# legoPFremote.net
KiCad netlist of a schematic drawn in EAGLE
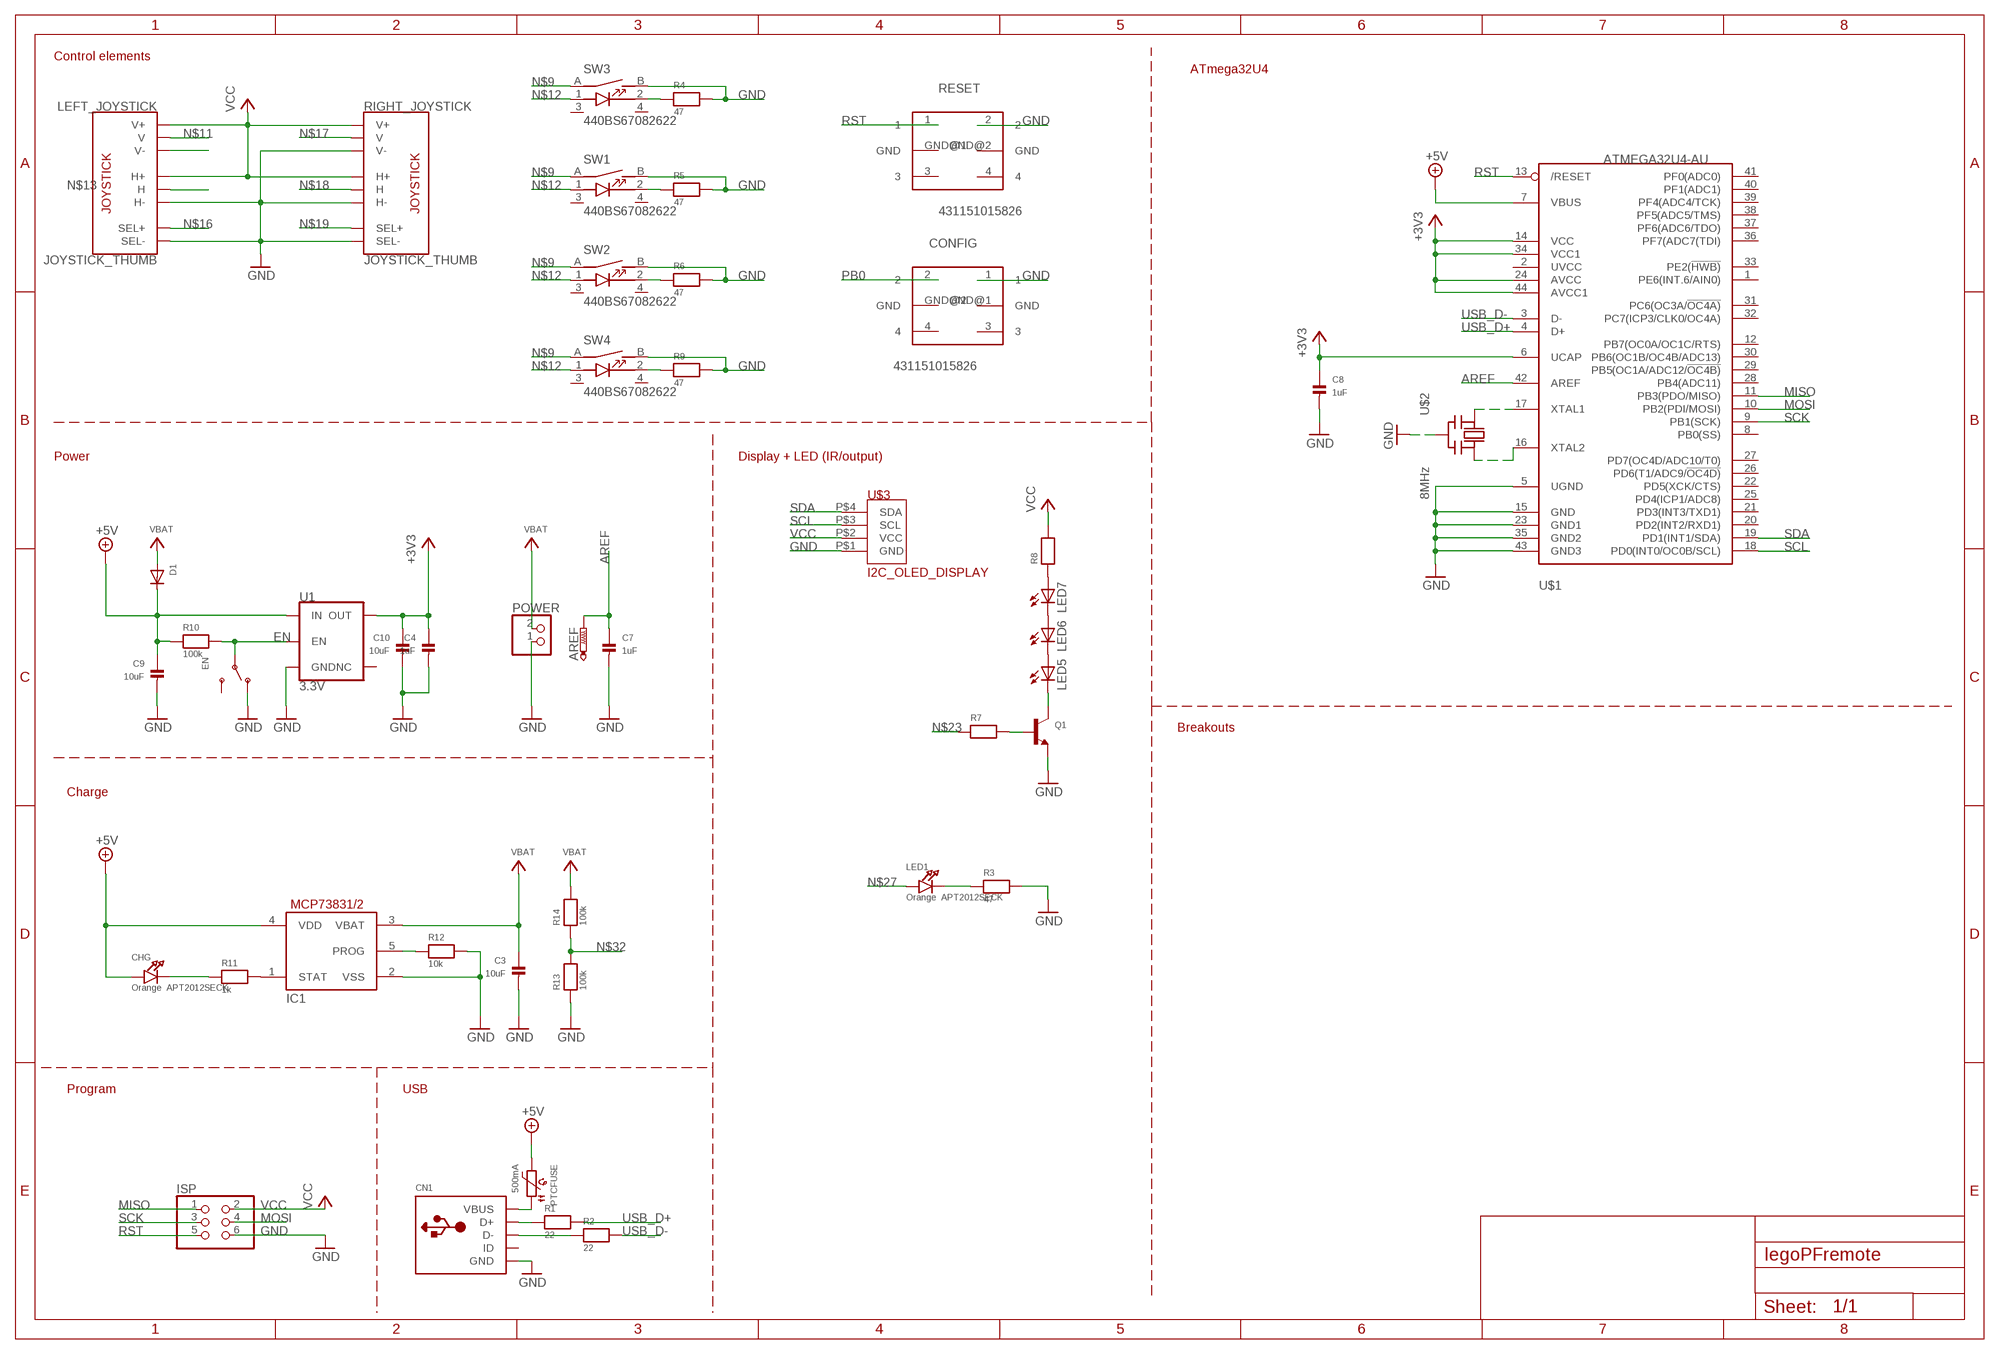
[diagram p0: schematic, sheet 1]

(export (version "E")
  (design (tool "Eeschema 10.0.6"))
  (components
    (comp (ref "AREF")
      (value "PTR1B1,27")
      (footprint "eagle-import:B1,27")
      (libsource (lib "eagle-import") (part "PTR1B1,27"))
    )
    (comp (ref "C3")
      (value "10uF")
      (footprint "eagle-import:0805")
      (libsource (lib "eagle-import") (part "CAP_CERAMIC0805"))
    )
    (comp (ref "C4")
      (value "1uF")
      (footprint "eagle-import:0805")
      (libsource (lib "eagle-import") (part "CAP_CERAMIC0805"))
    )
    (comp (ref "C7")
      (value "1uF")
      (footprint "eagle-import:0805")
      (libsource (lib "eagle-import") (part "CAP_CERAMIC0805"))
    )
    (comp (ref "C8")
      (value "1uF")
      (footprint "eagle-import:0805")
      (libsource (lib "eagle-import") (part "CAP_CERAMIC0805"))
    )
    (comp (ref "C9")
      (value "10uF")
      (footprint "eagle-import:0805")
      (libsource (lib "eagle-import") (part "CAP_CERAMIC0805"))
    )
    (comp (ref "C10")
      (value "10uF")
      (footprint "eagle-import:0805")
      (libsource (lib "eagle-import") (part "CAP_CERAMIC0805"))
    )
    (comp (ref "CHG")
      (value "Orange APT2012SECK")
      (footprint "eagle-import:CHIPLED_0805")
      (libsource (lib "eagle-import") (part "LED0805"))
    )
    (comp (ref "CN1")
      (value "USBMINIB")
      (footprint "eagle-import:USB-MINIB")
      (libsource (lib "eagle-import") (part "USBMINIB"))
    )
    (comp (ref "CONFIG")
      (value "431151015826")
      (footprint "eagle-import:431181015816")
      (libsource (lib "eagle-import") (part "431151015826"))
    )
    (comp (ref "D1")
      (value "DIODESOD-123")
      (footprint "eagle-import:SOD-123")
      (libsource (lib "eagle-import") (part "DIODESOD-123"))
    )
    (comp (ref "EN")
      (value "SWITCH_SPDT")
      (footprint "eagle-import:SPDT_SMT_SSSS811101")
      (libsource (lib "eagle-import") (part "SWITCH_SPDT"))
    )
    (comp (ref "IC1")
      (value "MCP73831/OT")
      (footprint "eagle-import:SOT23-5L")
      (libsource (lib "eagle-import") (part "MCP73831/OT"))
    )
    (comp (ref "ISP")
      (value "PINHD-2X3")
      (footprint "eagle-import:2X03")
      (libsource (lib "eagle-import") (part "PINHD-2X3"))
    )
    (comp (ref "LED1")
      (value "Orange APT2012SECK")
      (footprint "eagle-import:CHIPLED_0805")
      (libsource (lib "eagle-import") (part "LED0805"))
    )
    (comp (ref "LED5")
      (value "LEDIRL80A")
      (footprint "eagle-import:IRL80A")
      (libsource (lib "eagle-import") (part "LEDIRL80A"))
    )
    (comp (ref "LED6")
      (value "LEDIRL80A")
      (footprint "eagle-import:IRL80A")
      (libsource (lib "eagle-import") (part "LEDIRL80A"))
    )
    (comp (ref "LED7")
      (value "LEDIRL80A")
      (footprint "eagle-import:IRL80A")
      (libsource (lib "eagle-import") (part "LEDIRL80A"))
    )
    (comp (ref "LEFT_JOYSTICK")
      (value "JOYSTICK_THUMB")
      (footprint "eagle-import:JOYSTICK")
      (libsource (lib "eagle-import") (part "JOYSTICK_THUMB"))
    )
    (comp (ref "POWER")
      (value "JST_2PIN-THM")
      (footprint "eagle-import:JST-PH-2-THM")
      (libsource (lib "eagle-import") (part "JST_2PIN-THM"))
    )
    (comp (ref "PTCFUSE")
      (value "500mA")
      (footprint "eagle-import:1206")
      (libsource (lib "eagle-import") (part "PTC1206"))
    )
    (comp (ref "Q1")
      (value "TRANSISTOR_NPN")
      (footprint "eagle-import:SOT23-R")
      (libsource (lib "eagle-import") (part "TRANSISTOR_NPN"))
    )
    (comp (ref "R1")
      (value "22")
      (footprint "eagle-import:0805")
      (libsource (lib "eagle-import") (part "RESISTOR0805"))
    )
    (comp (ref "R2")
      (value "22")
      (footprint "eagle-import:0805")
      (libsource (lib "eagle-import") (part "RESISTOR0805"))
    )
    (comp (ref "R3")
      (value "47")
      (footprint "eagle-import:0805")
      (libsource (lib "eagle-import") (part "RESISTOR0805"))
    )
    (comp (ref "R4")
      (value "47")
      (footprint "eagle-import:0805")
      (libsource (lib "eagle-import") (part "RESISTOR0805"))
    )
    (comp (ref "R5")
      (value "47")
      (footprint "eagle-import:0805")
      (libsource (lib "eagle-import") (part "RESISTOR0805"))
    )
    (comp (ref "R6")
      (value "47")
      (footprint "eagle-import:0805")
      (libsource (lib "eagle-import") (part "RESISTOR0805"))
    )
    (comp (ref "R7")
      (value "RESISTOR0805")
      (footprint "eagle-import:0805")
      (libsource (lib "eagle-import") (part "RESISTOR0805"))
    )
    (comp (ref "R8")
      (value "RESISTOR0805")
      (footprint "eagle-import:0805")
      (libsource (lib "eagle-import") (part "RESISTOR0805"))
    )
    (comp (ref "R9")
      (value "47")
      (footprint "eagle-import:0805")
      (libsource (lib "eagle-import") (part "RESISTOR0805"))
    )
    (comp (ref "R10")
      (value "100k")
      (footprint "eagle-import:0805")
      (libsource (lib "eagle-import") (part "RESISTOR0805"))
    )
    (comp (ref "R11")
      (value "1k")
      (footprint "eagle-import:0805")
      (libsource (lib "eagle-import") (part "RESISTOR0805"))
    )
    (comp (ref "R12")
      (value "10k")
      (footprint "eagle-import:0805")
      (libsource (lib "eagle-import") (part "RESISTOR0805"))
    )
    (comp (ref "R13")
      (value "100k")
      (footprint "eagle-import:0805")
      (libsource (lib "eagle-import") (part "RESISTOR0805"))
    )
    (comp (ref "R14")
      (value "100k")
      (footprint "eagle-import:0805")
      (libsource (lib "eagle-import") (part "RESISTOR0805"))
    )
    (comp (ref "RESET")
      (value "431151015826")
      (footprint "eagle-import:431181015816")
      (libsource (lib "eagle-import") (part "431151015826"))
    )
    (comp (ref "RIGHT_JOYSTICK")
      (value "JOYSTICK_THUMB")
      (footprint "eagle-import:JOYSTICK")
      (libsource (lib "eagle-import") (part "JOYSTICK_THUMB"))
    )
    (comp (ref "SW1")
      (value "440BS67082622")
      (footprint "eagle-import:440BS67082622")
      (libsource (lib "eagle-import") (part "440BS67082622"))
    )
    (comp (ref "SW2")
      (value "440BS67082622")
      (footprint "eagle-import:440BS67082622")
      (libsource (lib "eagle-import") (part "440BS67082622"))
    )
    (comp (ref "SW3")
      (value "440BS67082622")
      (footprint "eagle-import:440BS67082622")
      (libsource (lib "eagle-import") (part "440BS67082622"))
    )
    (comp (ref "SW4")
      (value "440BS67082622")
      (footprint "eagle-import:440BS67082622")
      (libsource (lib "eagle-import") (part "440BS67082622"))
    )
    (comp (ref "U$1")
      (value "ATMEGA32U4-AU")
      (footprint "eagle-import:TQFP44")
      (libsource (lib "eagle-import") (part "ATMEGA32U4-AU"))
    )
    (comp (ref "U$2")
      (value "8MHz")
      (footprint "eagle-import:CSTCR-G")
      (libsource (lib "eagle-import") (part "CERMOSCILL-CSTCRG"))
    )
    (comp (ref "U$3")
      (value "I2C_OLED_DISPLAY")
      (footprint "eagle-import:HD1X4")
      (libsource (lib "eagle-import") (part "I2C_OLED_DISPLAY"))
    )
    (comp (ref "U1")
      (value "3.3V")
      (footprint "eagle-import:SOT23-5")
      (libsource (lib "eagle-import") (part "V_REG_AP2112K-3.3V"))
    )
  )
  (nets
    (net (code "1") (name "+3V3") (class "Default")
      (node (ref "C10") (pin "1") (pinfunction "P$1_1") (pintype "passive"))
      (node (ref "C4") (pin "1") (pinfunction "P$1_1") (pintype "passive"))
      (node (ref "C8") (pin "1") (pinfunction "P$1_1") (pintype "passive"))
      (node (ref "U$1") (pin "14") (pinfunction "VCC_14") (pintype "bidirectional"))
      (node (ref "U$1") (pin "24") (pinfunction "AVCC_24") (pintype "bidirectional"))
      (node (ref "U$1") (pin "34") (pinfunction "VCC1_34") (pintype "bidirectional"))
      (node (ref "U$1") (pin "44") (pinfunction "AVCC1_44") (pintype "bidirectional"))
      (node (ref "U$1") (pin "6") (pinfunction "UCAP_6") (pintype "bidirectional"))
      (node (ref "U1") (pin "5") (pinfunction "OUT_5") (pintype "passive"))
    )
    (net (code "2") (name "+5V") (class "Default")
      (node (ref "C9") (pin "1") (pinfunction "P$1_1") (pintype "passive"))
      (node (ref "CHG") (pin "A") (pinfunction "A_A") (pintype "passive"))
      (node (ref "D1") (pin "C") (pinfunction "C_C") (pintype "passive"))
      (node (ref "IC1") (pin "4") (pinfunction "VDD_4") (pintype "power_in"))
      (node (ref "PTCFUSE") (pin "2") (pinfunction "2_2") (pintype "passive"))
      (node (ref "R10") (pin "1") (pinfunction "1_1") (pintype "passive"))
      (node (ref "U$1") (pin "7") (pinfunction "VBUS_7") (pintype "bidirectional"))
      (node (ref "U1") (pin "1") (pinfunction "IN_1") (pintype "input"))
    )
    (net (code "3") (name "/AREF") (class "Default")
      (node (ref "AREF") (pin "TP") (pinfunction "TP_TP") (pintype "input"))
      (node (ref "C7") (pin "1") (pinfunction "P$1_1") (pintype "passive"))
      (node (ref "U$1") (pin "42") (pinfunction "AREF_42") (pintype "bidirectional"))
    )
    (net (code "4") (name "/EN") (class "Default")
      (node (ref "EN") (pin "B") (pinfunction "P_B") (pintype "passive"))
      (node (ref "R10") (pin "2") (pinfunction "2_2") (pintype "passive"))
      (node (ref "U1") (pin "3") (pinfunction "EN_3") (pintype "input"))
    )
    (net (code "5") (name "/MISO") (class "Default")
      (node (ref "ISP") (pin "1") (pinfunction "1_1") (pintype "passive"))
      (node (ref "U$1") (pin "11") (pinfunction "PB3(PDO/MISO)_11") (pintype "bidirectional"))
    )
    (net (code "6") (name "/MOSI") (class "Default")
      (node (ref "ISP") (pin "4") (pinfunction "4_4") (pintype "passive"))
      (node (ref "U$1") (pin "10") (pinfunction "PB2(PDI/MOSI)_10") (pintype "bidirectional"))
    )
    (net (code "7") (name "/N$9") (class "Default")
      (node (ref "SW1") (pin "A") (pinfunction "A_A") (pintype "passive"))
      (node (ref "SW2") (pin "A") (pinfunction "A_A") (pintype "passive"))
      (node (ref "SW3") (pin "A") (pinfunction "A_A") (pintype "passive"))
      (node (ref "SW4") (pin "A") (pinfunction "A_A") (pintype "passive"))
    )
    (net (code "8") (name "/N$11") (class "Default")
      (node (ref "LEFT_JOYSTICK") (pin "V2") (pinfunction "V_V2") (pintype "bidirectional"))
    )
    (net (code "9") (name "/N$12") (class "Default")
      (node (ref "SW1") (pin "1") (pinfunction "1_1") (pintype "passive"))
      (node (ref "SW2") (pin "1") (pinfunction "1_1") (pintype "passive"))
      (node (ref "SW3") (pin "1") (pinfunction "1_1") (pintype "passive"))
      (node (ref "SW4") (pin "1") (pinfunction "1_1") (pintype "passive"))
    )
    (net (code "10") (name "/N$13") (class "Default")
      (node (ref "LEFT_JOYSTICK") (pin "H2") (pinfunction "H_H2") (pintype "bidirectional"))
    )
    (net (code "11") (name "/N$16") (class "Default")
      (node (ref "LEFT_JOYSTICK") (pin "B1A") (pinfunction "SEL+_B1A") (pintype "bidirectional"))
    )
    (net (code "12") (name "/N$17") (class "Default")
      (node (ref "RIGHT_JOYSTICK") (pin "V2") (pinfunction "V_V2") (pintype "bidirectional"))
    )
    (net (code "13") (name "/N$18") (class "Default")
      (node (ref "RIGHT_JOYSTICK") (pin "H2") (pinfunction "H_H2") (pintype "bidirectional"))
    )
    (net (code "14") (name "/N$19") (class "Default")
      (node (ref "RIGHT_JOYSTICK") (pin "B1A") (pinfunction "SEL+_B1A") (pintype "bidirectional"))
    )
    (net (code "15") (name "/N$23") (class "Default")
      (node (ref "R7") (pin "1") (pinfunction "1_1") (pintype "passive"))
    )
    (net (code "16") (name "/N$27") (class "Default")
      (node (ref "LED1") (pin "A") (pinfunction "A_A") (pintype "passive"))
    )
    (net (code "17") (name "/N$32") (class "Default")
      (node (ref "R13") (pin "2") (pinfunction "2_2") (pintype "passive"))
      (node (ref "R14") (pin "1") (pinfunction "1_1") (pintype "passive"))
    )
    (net (code "18") (name "/PB0") (class "Default")
      (node (ref "CONFIG") (pin "2") (pinfunction "2_2") (pintype "bidirectional"))
    )
    (net (code "19") (name "/RST") (class "Default")
      (node (ref "ISP") (pin "5") (pinfunction "5_5") (pintype "passive"))
      (node (ref "RESET") (pin "1") (pinfunction "1_1") (pintype "bidirectional"))
      (node (ref "U$1") (pin "13") (pinfunction "/RESET_13") (pintype "bidirectional"))
    )
    (net (code "20") (name "/SCK") (class "Default")
      (node (ref "ISP") (pin "3") (pinfunction "3_3") (pintype "passive"))
      (node (ref "U$1") (pin "9") (pinfunction "PB1(SCK)_9") (pintype "bidirectional"))
    )
    (net (code "21") (name "/SCL") (class "Default")
      (node (ref "U$1") (pin "18") (pinfunction "PD0(INT0/OC0B/SCL)_18") (pintype "bidirectional"))
      (node (ref "U$3") (pin "P$3") (pinfunction "SCL_P$3") (pintype "bidirectional"))
    )
    (net (code "22") (name "/SDA") (class "Default")
      (node (ref "U$1") (pin "19") (pinfunction "PD1(INT1/SDA)_19") (pintype "bidirectional"))
      (node (ref "U$3") (pin "P$4") (pinfunction "SDA_P$4") (pintype "bidirectional"))
    )
    (net (code "23") (name "/USB_D+") (class "Default")
      (node (ref "R1") (pin "2") (pinfunction "2_2") (pintype "passive"))
      (node (ref "U$1") (pin "4") (pinfunction "D+_4") (pintype "bidirectional"))
    )
    (net (code "24") (name "/USB_D-") (class "Default")
      (node (ref "R2") (pin "2") (pinfunction "2_2") (pintype "passive"))
      (node (ref "U$1") (pin "3") (pinfunction "D-_3") (pintype "bidirectional"))
    )
    (net (code "25") (name "GND") (class "Default")
      (node (ref "C10") (pin "2") (pinfunction "P$2_2") (pintype "passive"))
      (node (ref "C3") (pin "2") (pinfunction "P$2_2") (pintype "passive"))
      (node (ref "C4") (pin "2") (pinfunction "P$2_2") (pintype "passive"))
      (node (ref "C7") (pin "2") (pinfunction "P$2_2") (pintype "passive"))
      (node (ref "C8") (pin "2") (pinfunction "P$2_2") (pintype "passive"))
      (node (ref "C9") (pin "2") (pinfunction "P$2_2") (pintype "passive"))
      (node (ref "CN1") (pin "GND") (pinfunction "GND_GND") (pintype "power_in"))
      (node (ref "CONFIG") (pin "1") (pinfunction "1_1") (pintype "bidirectional"))
      (node (ref "EN") (pin "A") (pinfunction "O_A") (pintype "passive"))
      (node (ref "IC1") (pin "2") (pinfunction "VSS_2") (pintype "power_in"))
      (node (ref "ISP") (pin "6") (pinfunction "6_6") (pintype "passive"))
      (node (ref "LEFT_JOYSTICK") (pin "B2A") (pinfunction "SEL-_B2A") (pintype "bidirectional"))
      (node (ref "LEFT_JOYSTICK") (pin "H3") (pinfunction "H-_H3") (pintype "bidirectional"))
      (node (ref "POWER") (pin "1") (pinfunction "2_1") (pintype "passive"))
      (node (ref "Q1") (pin "2") (pinfunction "E_2") (pintype "passive"))
      (node (ref "R12") (pin "2") (pinfunction "2_2") (pintype "passive"))
      (node (ref "R13") (pin "1") (pinfunction "1_1") (pintype "passive"))
      (node (ref "R3") (pin "2") (pinfunction "2_2") (pintype "passive"))
      (node (ref "R4") (pin "2") (pinfunction "2_2") (pintype "passive"))
      (node (ref "R5") (pin "2") (pinfunction "2_2") (pintype "passive"))
      (node (ref "R6") (pin "2") (pinfunction "2_2") (pintype "passive"))
      (node (ref "R9") (pin "2") (pinfunction "2_2") (pintype "passive"))
      (node (ref "RESET") (pin "2") (pinfunction "2_2") (pintype "bidirectional"))
      (node (ref "RIGHT_JOYSTICK") (pin "B2A") (pinfunction "SEL-_B2A") (pintype "bidirectional"))
      (node (ref "RIGHT_JOYSTICK") (pin "H3") (pinfunction "H-_H3") (pintype "bidirectional"))
      (node (ref "RIGHT_JOYSTICK") (pin "V3") (pinfunction "V-_V3") (pintype "bidirectional"))
      (node (ref "SW1") (pin "B") (pinfunction "B_B") (pintype "passive"))
      (node (ref "SW2") (pin "B") (pinfunction "B_B") (pintype "passive"))
      (node (ref "SW3") (pin "B") (pinfunction "B_B") (pintype "passive"))
      (node (ref "SW4") (pin "B") (pinfunction "B_B") (pintype "passive"))
      (node (ref "U$1") (pin "15") (pinfunction "GND_15") (pintype "bidirectional"))
      (node (ref "U$1") (pin "23") (pinfunction "GND1_23") (pintype "bidirectional"))
      (node (ref "U$1") (pin "35") (pinfunction "GND2_35") (pintype "bidirectional"))
      (node (ref "U$1") (pin "43") (pinfunction "GND3_43") (pintype "bidirectional"))
      (node (ref "U$1") (pin "5") (pinfunction "UGND_5") (pintype "bidirectional"))
      (node (ref "U$2") (pin "2") (pinfunction "GND_2") (pintype "bidirectional"))
      (node (ref "U$3") (pin "P$1") (pinfunction "GND_P$1") (pintype "bidirectional"))
      (node (ref "U1") (pin "2") (pinfunction "GND_2") (pintype "input"))
    )
    (net (code "26") (name "Net-(CHG-PadC)") (class "Default")
      (node (ref "CHG") (pin "C") (pinfunction "C_C") (pintype "passive"))
      (node (ref "R11") (pin "1") (pinfunction "1_1") (pintype "passive"))
    )
    (net (code "27") (name "Net-(CN1-PadD+)") (class "Default")
      (node (ref "CN1") (pin "D+") (pinfunction "D+_D+") (pintype "bidirectional"))
      (node (ref "R1") (pin "1") (pinfunction "1_1") (pintype "passive"))
    )
    (net (code "28") (name "Net-(CN1-PadD-)") (class "Default")
      (node (ref "CN1") (pin "D-") (pinfunction "D-_D-") (pintype "bidirectional"))
      (node (ref "R2") (pin "1") (pinfunction "1_1") (pintype "passive"))
    )
    (net (code "29") (name "Net-(CN1-PadVBUS)") (class "Default")
      (node (ref "CN1") (pin "VBUS") (pinfunction "VBUS_VBUS") (pintype "power_in"))
      (node (ref "PTCFUSE") (pin "1") (pinfunction "1_1") (pintype "passive"))
    )
    (net (code "30") (name "Net-(IC1-PROG)") (class "Default")
      (node (ref "IC1") (pin "5") (pinfunction "PROG_5") (pintype "input"))
      (node (ref "R12") (pin "1") (pinfunction "1_1") (pintype "passive"))
    )
    (net (code "31") (name "Net-(IC1-STAT)") (class "Default")
      (node (ref "IC1") (pin "1") (pinfunction "STAT_1") (pintype "output"))
      (node (ref "R11") (pin "2") (pinfunction "2_2") (pintype "passive"))
    )
    (net (code "32") (name "Net-(LED1-PadC)") (class "Default")
      (node (ref "LED1") (pin "C") (pinfunction "C_C") (pintype "passive"))
      (node (ref "R3") (pin "1") (pinfunction "1_1") (pintype "passive"))
    )
    (net (code "33") (name "Net-(LED5-C)") (class "Default")
      (node (ref "LED5") (pin "K") (pinfunction "C_K") (pintype "passive"))
      (node (ref "Q1") (pin "3") (pinfunction "C_3") (pintype "passive"))
    )
    (net (code "34") (name "Net-(LED6-C)") (class "Default")
      (node (ref "LED5") (pin "A") (pinfunction "A_A") (pintype "passive"))
      (node (ref "LED6") (pin "K") (pinfunction "C_K") (pintype "passive"))
    )
    (net (code "35") (name "Net-(LED7-C)") (class "Default")
      (node (ref "LED6") (pin "A") (pinfunction "A_A") (pintype "passive"))
      (node (ref "LED7") (pin "K") (pinfunction "C_K") (pintype "passive"))
    )
    (net (code "36") (name "Net-(LED7-PadA)") (class "Default")
      (node (ref "LED7") (pin "A") (pinfunction "A_A") (pintype "passive"))
      (node (ref "R8") (pin "1") (pinfunction "1_1") (pintype "passive"))
    )
    (net (code "37") (name "Net-(Q1-B)") (class "Default")
      (node (ref "Q1") (pin "1") (pinfunction "B_1") (pintype "passive"))
      (node (ref "R7") (pin "2") (pinfunction "2_2") (pintype "passive"))
    )
    (net (code "38") (name "Net-(R4-Pad1)") (class "Default")
      (node (ref "R4") (pin "1") (pinfunction "1_1") (pintype "passive"))
      (node (ref "SW3") (pin "2") (pinfunction "2_2") (pintype "passive"))
    )
    (net (code "39") (name "Net-(R5-Pad1)") (class "Default")
      (node (ref "R5") (pin "1") (pinfunction "1_1") (pintype "passive"))
      (node (ref "SW1") (pin "2") (pinfunction "2_2") (pintype "passive"))
    )
    (net (code "40") (name "Net-(R6-Pad1)") (class "Default")
      (node (ref "R6") (pin "1") (pinfunction "1_1") (pintype "passive"))
      (node (ref "SW2") (pin "2") (pinfunction "2_2") (pintype "passive"))
    )
    (net (code "41") (name "Net-(R9-Pad1)") (class "Default")
      (node (ref "R9") (pin "1") (pinfunction "1_1") (pintype "passive"))
      (node (ref "SW4") (pin "2") (pinfunction "2_2") (pintype "passive"))
    )
    (net (code "42") (name "Net-(U$1-XTAL1)") (class "Default")
      (node (ref "U$1") (pin "17") (pinfunction "XTAL1_17") (pintype "bidirectional"))
      (node (ref "U$2") (pin "1") (pinfunction "IN_1") (pintype "bidirectional"))
    )
    (net (code "43") (name "Net-(U$1-XTAL2)") (class "Default")
      (node (ref "U$1") (pin "16") (pinfunction "XTAL2_16") (pintype "bidirectional"))
      (node (ref "U$2") (pin "3") (pinfunction "OUT_3") (pintype "bidirectional"))
    )
    (net (code "44") (name "VBAT") (class "Default")
      (node (ref "C3") (pin "1") (pinfunction "P$1_1") (pintype "passive"))
      (node (ref "D1") (pin "A") (pinfunction "A_A") (pintype "passive"))
      (node (ref "IC1") (pin "3") (pinfunction "VBAT_3") (pintype "bidirectional"))
      (node (ref "POWER") (pin "2") (pinfunction "1_2") (pintype "passive"))
      (node (ref "R14") (pin "2") (pinfunction "2_2") (pintype "passive"))
    )
    (net (code "45") (name "VCC") (class "Default")
      (node (ref "ISP") (pin "2") (pinfunction "2_2") (pintype "passive"))
      (node (ref "LEFT_JOYSTICK") (pin "H1") (pinfunction "H+_H1") (pintype "bidirectional"))
      (node (ref "LEFT_JOYSTICK") (pin "V1") (pinfunction "V+_V1") (pintype "bidirectional"))
      (node (ref "R8") (pin "2") (pinfunction "2_2") (pintype "passive"))
      (node (ref "RIGHT_JOYSTICK") (pin "H1") (pinfunction "H+_H1") (pintype "bidirectional"))
      (node (ref "RIGHT_JOYSTICK") (pin "V1") (pinfunction "V+_V1") (pintype "bidirectional"))
      (node (ref "U$3") (pin "P$2") (pinfunction "VCC_P$2") (pintype "bidirectional"))
    )
    (net (code "46") (name "unconnected-(CN1-PadID)") (class "Default")
      (node (ref "CN1") (pin "ID") (pinfunction "ID_ID") (pintype "bidirectional"))
    )
    (net (code "47") (name "unconnected-(CONFIG-GND-PadGND@1)") (class "Default")
      (node (ref "CONFIG") (pin "GND@1") (pinfunction "GND_GND@1") (pintype "bidirectional"))
    )
    (net (code "48") (name "unconnected-(CONFIG-GND-PadGND@2)") (class "Default")
      (node (ref "CONFIG") (pin "GND@2") (pinfunction "GND_GND@2") (pintype "bidirectional"))
    )
    (net (code "49") (name "unconnected-(CONFIG-Pad3)") (class "Default")
      (node (ref "CONFIG") (pin "3") (pinfunction "3_3") (pintype "bidirectional"))
    )
    (net (code "50") (name "unconnected-(CONFIG-Pad4)") (class "Default")
      (node (ref "CONFIG") (pin "4") (pinfunction "4_4") (pintype "bidirectional"))
    )
    (net (code "51") (name "unconnected-(EN-S-PadC)") (class "Default")
      (node (ref "EN") (pin "C") (pinfunction "S_C") (pintype "passive"))
    )
    (net (code "52") (name "unconnected-(LEFT_JOYSTICK-V--PadV3)") (class "Default")
      (node (ref "LEFT_JOYSTICK") (pin "V3") (pinfunction "V-_V3") (pintype "bidirectional"))
    )
    (net (code "53") (name "unconnected-(RESET-GND-PadGND@1)") (class "Default")
      (node (ref "RESET") (pin "GND@1") (pinfunction "GND_GND@1") (pintype "bidirectional"))
    )
    (net (code "54") (name "unconnected-(RESET-GND-PadGND@2)") (class "Default")
      (node (ref "RESET") (pin "GND@2") (pinfunction "GND_GND@2") (pintype "bidirectional"))
    )
    (net (code "55") (name "unconnected-(RESET-Pad3)") (class "Default")
      (node (ref "RESET") (pin "3") (pinfunction "3_3") (pintype "bidirectional"))
    )
    (net (code "56") (name "unconnected-(RESET-Pad4)") (class "Default")
      (node (ref "RESET") (pin "4") (pinfunction "4_4") (pintype "bidirectional"))
    )
    (net (code "57") (name "unconnected-(SW1-Pad3)") (class "Default")
      (node (ref "SW1") (pin "3") (pinfunction "3_3") (pintype "no_connect"))
    )
    (net (code "58") (name "unconnected-(SW1-Pad4)") (class "Default")
      (node (ref "SW1") (pin "4") (pinfunction "4_4") (pintype "no_connect"))
    )
    (net (code "59") (name "unconnected-(SW2-Pad3)") (class "Default")
      (node (ref "SW2") (pin "3") (pinfunction "3_3") (pintype "no_connect"))
    )
    (net (code "60") (name "unconnected-(SW2-Pad4)") (class "Default")
      (node (ref "SW2") (pin "4") (pinfunction "4_4") (pintype "no_connect"))
    )
    (net (code "61") (name "unconnected-(SW3-Pad3)") (class "Default")
      (node (ref "SW3") (pin "3") (pinfunction "3_3") (pintype "no_connect"))
    )
    (net (code "62") (name "unconnected-(SW3-Pad4)") (class "Default")
      (node (ref "SW3") (pin "4") (pinfunction "4_4") (pintype "no_connect"))
    )
    (net (code "63") (name "unconnected-(SW4-Pad3)") (class "Default")
      (node (ref "SW4") (pin "3") (pinfunction "3_3") (pintype "no_connect"))
    )
    (net (code "64") (name "unconnected-(SW4-Pad4)") (class "Default")
      (node (ref "SW4") (pin "4") (pinfunction "4_4") (pintype "no_connect"))
    )
    (net (code "65") (name "unconnected-(U$1-PB0(SS)-Pad8)") (class "Default")
      (node (ref "U$1") (pin "8") (pinfunction "PB0(SS)_8") (pintype "bidirectional"))
    )
    (net (code "66") (name "unconnected-(U$1-PB4(ADC11)-Pad28)") (class "Default")
      (node (ref "U$1") (pin "28") (pinfunction "PB4(ADC11)_28") (pintype "bidirectional"))
    )
    (net (code "67") (name "unconnected-(U$1-PB5(OC1A{slash}ADC12{slash}~{OC4B})-Pad29)") (class "Default")
      (node (ref "U$1") (pin "29") (pinfunction "PB5(OC1A/ADC12/~{OC4B})_29") (pintype "bidirectional"))
    )
    (net (code "68") (name "unconnected-(U$1-PB6(OC1B{slash}OC4B{slash}ADC13)-Pad30)") (class "Default")
      (node (ref "U$1") (pin "30") (pinfunction "PB6(OC1B/OC4B/ADC13)_30") (pintype "bidirectional"))
    )
    (net (code "69") (name "unconnected-(U$1-PB7(OC0A{slash}OC1C{slash}RTS)-Pad12)") (class "Default")
      (node (ref "U$1") (pin "12") (pinfunction "PB7(OC0A/OC1C/RTS)_12") (pintype "bidirectional"))
    )
    (net (code "70") (name "unconnected-(U$1-PC6(OC3A{slash}~{OC4A})-Pad31)") (class "Default")
      (node (ref "U$1") (pin "31") (pinfunction "PC6(OC3A/~{OC4A})_31") (pintype "bidirectional"))
    )
    (net (code "71") (name "unconnected-(U$1-PC7(ICP3{slash}CLK0{slash}OC4A)-Pad32)") (class "Default")
      (node (ref "U$1") (pin "32") (pinfunction "PC7(ICP3/CLK0/OC4A)_32") (pintype "bidirectional"))
    )
    (net (code "72") (name "unconnected-(U$1-PD2(INT2{slash}RXD1)-Pad20)") (class "Default")
      (node (ref "U$1") (pin "20") (pinfunction "PD2(INT2/RXD1)_20") (pintype "bidirectional"))
    )
    (net (code "73") (name "unconnected-(U$1-PD3(INT3{slash}TXD1)-Pad21)") (class "Default")
      (node (ref "U$1") (pin "21") (pinfunction "PD3(INT3/TXD1)_21") (pintype "bidirectional"))
    )
    (net (code "74") (name "unconnected-(U$1-PD4(ICP1{slash}ADC8)-Pad25)") (class "Default")
      (node (ref "U$1") (pin "25") (pinfunction "PD4(ICP1/ADC8)_25") (pintype "bidirectional"))
    )
    (net (code "75") (name "unconnected-(U$1-PD5(XCK{slash}CTS)-Pad22)") (class "Default")
      (node (ref "U$1") (pin "22") (pinfunction "PD5(XCK/CTS)_22") (pintype "bidirectional"))
    )
    (net (code "76") (name "unconnected-(U$1-PD6(T1{slash}ADC9{slash}~{OC4D})-Pad26)") (class "Default")
      (node (ref "U$1") (pin "26") (pinfunction "PD6(T1/ADC9/~{OC4D})_26") (pintype "bidirectional"))
    )
    (net (code "77") (name "unconnected-(U$1-PD7(OC4D{slash}ADC10{slash}T0)-Pad27)") (class "Default")
      (node (ref "U$1") (pin "27") (pinfunction "PD7(OC4D/ADC10/T0)_27") (pintype "bidirectional"))
    )
    (net (code "78") (name "unconnected-(U$1-PE2(~{HWB})-Pad33)") (class "Default")
      (node (ref "U$1") (pin "33") (pinfunction "PE2(~{HWB})_33") (pintype "bidirectional"))
    )
    (net (code "79") (name "unconnected-(U$1-PE6(INT.6{slash}AIN0)-Pad1)") (class "Default")
      (node (ref "U$1") (pin "1") (pinfunction "PE6(INT.6/AIN0)_1") (pintype "bidirectional"))
    )
    (net (code "80") (name "unconnected-(U$1-PF0(ADC0)-Pad41)") (class "Default")
      (node (ref "U$1") (pin "41") (pinfunction "PF0(ADC0)_41") (pintype "bidirectional"))
    )
    (net (code "81") (name "unconnected-(U$1-PF1(ADC1)-Pad40)") (class "Default")
      (node (ref "U$1") (pin "40") (pinfunction "PF1(ADC1)_40") (pintype "bidirectional"))
    )
    (net (code "82") (name "unconnected-(U$1-PF4(ADC4{slash}TCK)-Pad39)") (class "Default")
      (node (ref "U$1") (pin "39") (pinfunction "PF4(ADC4/TCK)_39") (pintype "bidirectional"))
    )
    (net (code "83") (name "unconnected-(U$1-PF5(ADC5{slash}TMS)-Pad38)") (class "Default")
      (node (ref "U$1") (pin "38") (pinfunction "PF5(ADC5/TMS)_38") (pintype "bidirectional"))
    )
    (net (code "84") (name "unconnected-(U$1-PF6(ADC6{slash}TDO)-Pad37)") (class "Default")
      (node (ref "U$1") (pin "37") (pinfunction "PF6(ADC6/TDO)_37") (pintype "bidirectional"))
    )
    (net (code "85") (name "unconnected-(U$1-PF7(ADC7(TDI)-Pad36)") (class "Default")
      (node (ref "U$1") (pin "36") (pinfunction "PF7(ADC7(TDI)_36") (pintype "bidirectional"))
    )
    (net (code "86") (name "unconnected-(U$1-UVCC-Pad2)") (class "Default")
      (node (ref "U$1") (pin "2") (pinfunction "UVCC_2") (pintype "bidirectional"))
    )
    (net (code "87") (name "unconnected-(U1-NC-Pad4)") (class "Default")
      (node (ref "U1") (pin "4") (pinfunction "NC_4") (pintype "no_connect"))
    )
  )
)
